# Dimmer_atmega328.net
KiCad netlist of a schematic drawn in EAGLE
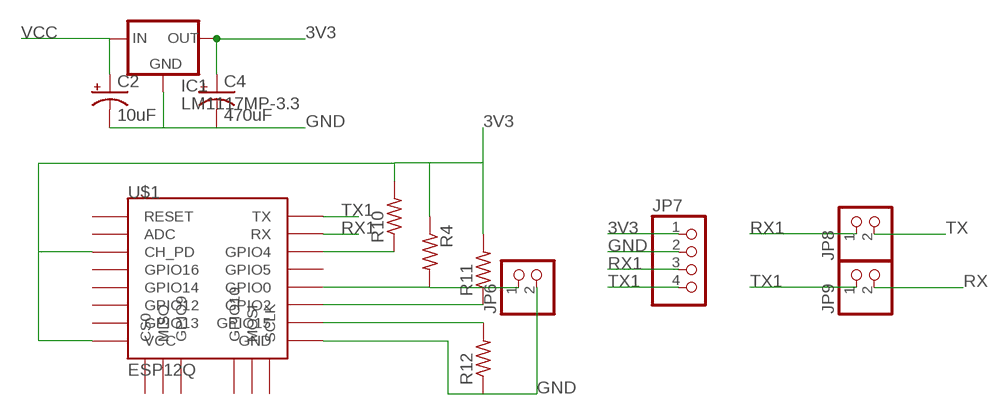
[diagram p0: schematic, sheet 1]
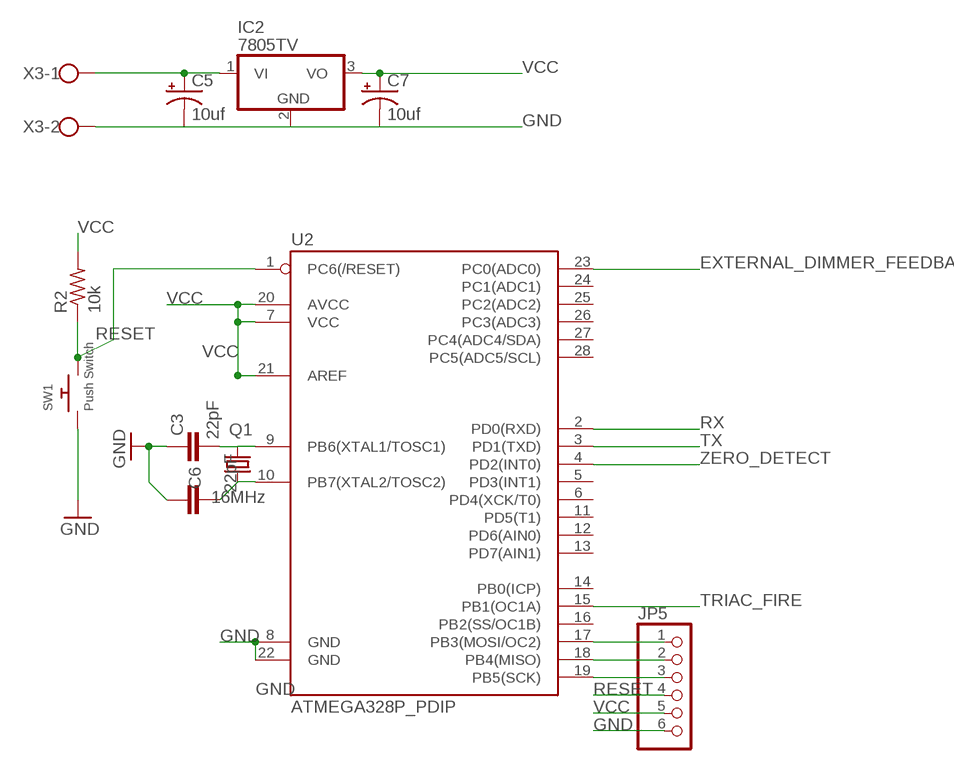
[diagram p1: schematic, sheet 2]
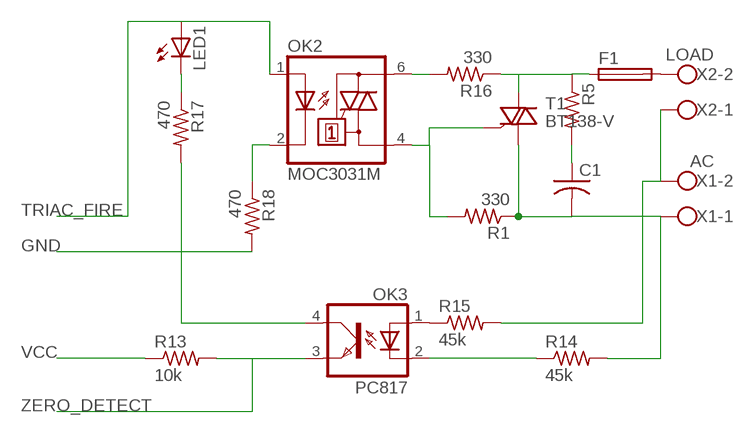
[diagram p2: schematic, sheet 3]
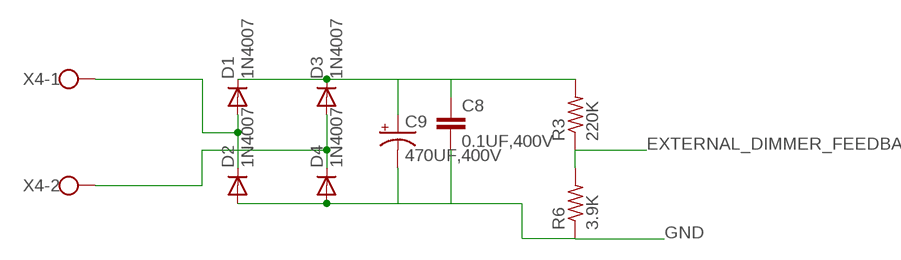
[diagram p3: schematic, sheet 4]

(export (version "E")
  (design (tool "Eeschema 10.0.6"))
  (components
    (comp (ref "C3")
      (value "22pF")
      (footprint "eagle-import:CAP-PTH-SMALL")
      (libsource (lib "eagle-import") (part "CAPPTH"))
    )
    (comp (ref "C5")
      (value "10uf")
      (footprint "eagle-import:E2,5-6")
      (libsource (lib "eagle-import") (part "rcl_CPOL-USE2.5-6"))
    )
    (comp (ref "C6")
      (value "22pF")
      (footprint "eagle-import:CAP-PTH-SMALL")
      (libsource (lib "eagle-import") (part "CAPPTH"))
    )
    (comp (ref "C7")
      (value "10uf")
      (footprint "eagle-import:E2,5-6")
      (libsource (lib "eagle-import") (part "rcl_CPOL-USE2.5-6"))
    )
    (comp (ref "IC2")
      (value "7805TV")
      (footprint "eagle-import:TO220V")
      (libsource (lib "eagle-import") (part "78TV05"))
    )
    (comp (ref "JP5")
      (value "PINHD-1X6")
      (footprint "eagle-import:1X06")
      (libsource (lib "eagle-import") (part "PINHD-1X6"))
    )
    (comp (ref "Q1")
      (value "16MHz")
      (footprint "eagle-import:HC49US")
      (libsource (lib "eagle-import") (part "CRYSTALHC49US"))
    )
    (comp (ref "R2")
      (value "10k")
      (footprint "eagle-import:0207_10")
      (libsource (lib "eagle-import") (part "resistor_R-US_0207/10"))
    )
    (comp (ref "SW1")
      (value "Push Switch")
      (footprint "eagle-import:TACT_PANA-EVQ")
      (libsource (lib "eagle-import") (part "SWITCH_PUSHBUTTONEVQ-PE"))
    )
    (comp (ref "U2")
      (value "ATMEGA328P_PDIP")
      (footprint "eagle-import:DIL28-3")
      (libsource (lib "eagle-import") (part "ATMEGA328P_PDIP"))
    )
    (comp (ref "X3")
      (value "W237-102")
      (footprint "eagle-import:W237-102")
      (fields (field (name "MPN") "237-102"))
      (libsource (lib "eagle-import") (part "con-wago-500_W237-102"))
    )
    (comp (ref "C8")
      (value "0.1UF,400V")
      (footprint "eagle-import:C102-054X133")
      (libsource (lib "eagle-import") (part "C-EU102-054X133"))
    )
    (comp (ref "C9")
      (value "470UF,400V")
      (footprint "eagle-import:E7,5-18")
      (libsource (lib "eagle-import") (part "CPOL-USE7.5-18"))
    )
    (comp (ref "D1")
      (value "1N4007")
      (footprint "eagle-import:DO41-10")
      (libsource (lib "eagle-import") (part "1N4004"))
    )
    (comp (ref "D2")
      (value "1N4007")
      (footprint "eagle-import:DO41-10")
      (libsource (lib "eagle-import") (part "1N4004"))
    )
    (comp (ref "D3")
      (value "1N4007")
      (footprint "eagle-import:DO41-10")
      (libsource (lib "eagle-import") (part "1N4004"))
    )
    (comp (ref "D4")
      (value "1N4007")
      (footprint "eagle-import:DO41-10")
      (libsource (lib "eagle-import") (part "1N4004"))
    )
    (comp (ref "R3")
      (value "220K")
      (footprint "eagle-import:0207_10")
      (libsource (lib "eagle-import") (part "R-US_0207/10"))
    )
    (comp (ref "R6")
      (value "3.9K")
      (footprint "eagle-import:0207_10")
      (libsource (lib "eagle-import") (part "R-US_0207/10"))
    )
    (comp (ref "X4")
      (value "W237-102")
      (footprint "eagle-import:W237-102")
      (fields (field (name "MPN") "237-102"))
      (libsource (lib "eagle-import") (part "W237-102"))
    )
    (comp (ref "C2")
      (value "10uF")
      (footprint "eagle-import:E2,5-6")
      (libsource (lib "eagle-import") (part "rcl_CPOL-USE2.5-6"))
    )
    (comp (ref "C4")
      (value "470uF")
      (footprint "eagle-import:E5-8,5")
      (libsource (lib "eagle-import") (part "rcl_CPOL-USE5-8.5"))
    )
    (comp (ref "IC1")
      (value "LM1117MP-3.3")
      (footprint "eagle-import:SOT223")
      (fields (field (name "MF") "Texas Instruments"))
      (libsource (lib "eagle-import") (part "LM1117?-MP3.3"))
    )
    (comp (ref "JP6")
      (value "PINHD-1X2")
      (footprint "eagle-import:1X02")
      (libsource (lib "eagle-import") (part "PINHD-1X2"))
    )
    (comp (ref "JP7")
      (value "PINHD-1X4")
      (footprint "eagle-import:1X04")
      (libsource (lib "eagle-import") (part "PINHD-1X4"))
    )
    (comp (ref "JP8")
      (value "PINHD-1X2")
      (footprint "eagle-import:1X02")
      (libsource (lib "eagle-import") (part "PINHD-1X2"))
    )
    (comp (ref "JP9")
      (value "PINHD-1X2")
      (footprint "eagle-import:1X02")
      (libsource (lib "eagle-import") (part "PINHD-1X2"))
    )
    (comp (ref "R4")
      (value "R-US_0207/10")
      (footprint "eagle-import:0207_10")
      (libsource (lib "eagle-import") (part "rcl_R-US_0207/10"))
    )
    (comp (ref "R10")
      (value "R-US_0207/10")
      (footprint "eagle-import:0207_10")
      (libsource (lib "eagle-import") (part "rcl_R-US_0207/10"))
    )
    (comp (ref "R11")
      (value "R-US_0207/10")
      (footprint "eagle-import:0207_10")
      (libsource (lib "eagle-import") (part "rcl_R-US_0207/10"))
    )
    (comp (ref "R12")
      (value "R-US_0207/10")
      (footprint "eagle-import:0207_10")
      (libsource (lib "eagle-import") (part "rcl_R-US_0207/10"))
    )
    (comp (ref "U$1")
      (value "ESP12Q")
      (footprint "eagle-import:ESP12Q")
      (libsource (lib "eagle-import") (part "ESP12Q"))
    )
    (comp (ref "C1")
      (value "C-US150-091X182")
      (footprint "eagle-import:C150-091X182")
      (libsource (lib "eagle-import") (part "C-US150-091X182"))
    )
    (comp (ref "F1")
      (value "GSH15")
      (footprint "eagle-import:GSH15")
      (fields (field (name "MPN") "64900001039"))
      (libsource (lib "eagle-import") (part "GSH15"))
    )
    (comp (ref "LED1")
      (value "LED3MM")
      (footprint "eagle-import:LED3MM")
      (libsource (lib "eagle-import") (part "LED3MM"))
    )
    (comp (ref "OK2")
      (value "MOC3031M")
      (footprint "eagle-import:DIL06")
      (fields (field (name "MF") "FAIRCHILD SEMICONDUCTOR"))
      (libsource (lib "eagle-import") (part "MOC3031M"))
    )
    (comp (ref "OK3")
      (value "PC817")
      (footprint "eagle-import:DIL04")
      (fields (field (name "MPN") "PC817X4J000F"))
      (libsource (lib "eagle-import") (part "PC817"))
    )
    (comp (ref "R1")
      (value "330")
      (footprint "eagle-import:0207_10")
      (libsource (lib "eagle-import") (part "resistor_R-US_0207/10"))
    )
    (comp (ref "R5")
      (value "R-US_0411/15")
      (footprint "eagle-import:0411_15")
      (libsource (lib "eagle-import") (part "resistor_R-US_0411/15"))
    )
    (comp (ref "R13")
      (value "10k")
      (footprint "eagle-import:0207_10")
      (libsource (lib "eagle-import") (part "resistor_R-US_0207/10"))
    )
    (comp (ref "R14")
      (value "45k")
      (footprint "eagle-import:0207_10")
      (libsource (lib "eagle-import") (part "resistor_R-US_0207/10"))
    )
    (comp (ref "R15")
      (value "45k")
      (footprint "eagle-import:0207_10")
      (libsource (lib "eagle-import") (part "resistor_R-US_0207/10"))
    )
    (comp (ref "R16")
      (value "330")
      (footprint "eagle-import:0207_10")
      (libsource (lib "eagle-import") (part "resistor_R-US_0207/10"))
    )
    (comp (ref "R17")
      (value "470")
      (footprint "eagle-import:0207_10")
      (libsource (lib "eagle-import") (part "resistor_R-US_0207/10"))
    )
    (comp (ref "R18")
      (value "470")
      (footprint "eagle-import:0207_10")
      (libsource (lib "eagle-import") (part "resistor_R-US_0207/10"))
    )
    (comp (ref "T1")
      (value "BT138-V")
      (footprint "eagle-import:TO220BV")
      (libsource (lib "eagle-import") (part "BT138-V"))
    )
    (comp (ref "X1")
      (value "AC")
      (footprint "eagle-import:W237-102")
      (fields (field (name "MPN") "237-102"))
      (libsource (lib "eagle-import") (part "con-wago-500_W237-102"))
    )
    (comp (ref "X2")
      (value "LOAD")
      (footprint "eagle-import:W237-102")
      (fields (field (name "MPN") "237-102"))
      (libsource (lib "eagle-import") (part "con-wago-500_W237-102"))
    )
  )
  (nets
    (net (code "1") (name "3V3") (class "Default")
      (node (ref "C4") (pin "+") (pinfunction "+_+") (pintype "passive"))
      (node (ref "IC1") (pin "2") (pinfunction "OUT_2") (pintype "passive"))
      (node (ref "IC1") (pin "4") (pinfunction "OUT_4") (pintype "passive"))
      (node (ref "JP7") (pin "1") (pinfunction "1_1") (pintype "passive"))
      (node (ref "R10") (pin "2") (pinfunction "2_2") (pintype "passive"))
      (node (ref "R11") (pin "2") (pinfunction "2_2") (pintype "passive"))
      (node (ref "R4") (pin "1") (pinfunction "1_1") (pintype "passive"))
      (node (ref "U$1") (pin "CH_PD") (pinfunction "CH_PD_CH_PD") (pintype "bidirectional"))
      (node (ref "U$1") (pin "VCC") (pinfunction "VCC_VCC") (pintype "bidirectional"))
    )
    (net (code "2") (name "EXTERNAL_DIMMER_FEEDBACK") (class "Default")
      (node (ref "R3") (pin "1") (pinfunction "1_1") (pintype "passive"))
      (node (ref "R6") (pin "2") (pinfunction "2_2") (pintype "passive"))
      (node (ref "U2") (pin "23") (pinfunction "PC0(ADC0)_23") (pintype "bidirectional"))
    )
    (net (code "3") (name "GND") (class "Default")
      (node (ref "C2") (pin "-") (pinfunction "-_-") (pintype "passive"))
      (node (ref "C3") (pin "1") (pinfunction "1_1") (pintype "passive"))
      (node (ref "C4") (pin "-") (pinfunction "-_-") (pintype "passive"))
      (node (ref "C5") (pin "-") (pinfunction "-_-") (pintype "passive"))
      (node (ref "C6") (pin "1") (pinfunction "1_1") (pintype "passive"))
      (node (ref "C7") (pin "-") (pinfunction "-_-") (pintype "passive"))
      (node (ref "C8") (pin "2") (pinfunction "2_2") (pintype "passive"))
      (node (ref "C9") (pin "-") (pinfunction "-_-") (pintype "passive"))
      (node (ref "D2") (pin "A") (pinfunction "A_A") (pintype "passive"))
      (node (ref "D4") (pin "A") (pinfunction "A_A") (pintype "passive"))
      (node (ref "IC1") (pin "1") (pinfunction "GND_1") (pintype "input"))
      (node (ref "IC2") (pin "2") (pinfunction "GND_2") (pintype "passive"))
      (node (ref "JP5") (pin "6") (pinfunction "6_6") (pintype "passive"))
      (node (ref "JP6") (pin "2") (pinfunction "2_2") (pintype "passive"))
      (node (ref "JP7") (pin "2") (pinfunction "2_2") (pintype "passive"))
      (node (ref "OK3") (pin "4") (pinfunction "COL_4") (pintype "passive"))
      (node (ref "R12") (pin "1") (pinfunction "1_1") (pintype "passive"))
      (node (ref "R17") (pin "2") (pinfunction "2_2") (pintype "passive"))
      (node (ref "R18") (pin "2") (pinfunction "2_2") (pintype "passive"))
      (node (ref "R6") (pin "1") (pinfunction "1_1") (pintype "passive"))
      (node (ref "SW1") (pin "P$1") (pinfunction "P$1_P$1") (pintype "passive"))
      (node (ref "U$1") (pin "GND") (pinfunction "GND_GND") (pintype "bidirectional"))
      (node (ref "U2") (pin "22") (pinfunction "GND_22") (pintype "bidirectional"))
      (node (ref "U2") (pin "8") (pinfunction "GND_8") (pintype "bidirectional"))
      (node (ref "X3") (pin "2") (pinfunction "KL_2") (pintype "passive"))
    )
    (net (code "4") (name "Net-(C1-Pad1)") (class "Default")
      (node (ref "C1") (pin "1") (pinfunction "1_1") (pintype "passive"))
      (node (ref "R5") (pin "2") (pinfunction "2_2") (pintype "passive"))
    )
    (net (code "5") (name "Net-(C8-Pad1)") (class "Default")
      (node (ref "C8") (pin "1") (pinfunction "1_1") (pintype "passive"))
      (node (ref "C9") (pin "+") (pinfunction "+_+") (pintype "passive"))
      (node (ref "D1") (pin "C") (pinfunction "C_C") (pintype "passive"))
      (node (ref "D3") (pin "C") (pinfunction "C_C") (pintype "passive"))
      (node (ref "R3") (pin "2") (pinfunction "2_2") (pintype "passive"))
    )
    (net (code "6") (name "Net-(IC2-VI)") (class "Default")
      (node (ref "C5") (pin "+") (pinfunction "+_+") (pintype "passive"))
      (node (ref "IC2") (pin "1") (pinfunction "VI_1") (pintype "input"))
      (node (ref "X3") (pin "1") (pinfunction "KL_1") (pintype "passive"))
    )
    (net (code "7") (name "Net-(JP6-Pad1)") (class "Default")
      (node (ref "JP6") (pin "1") (pinfunction "1_1") (pintype "passive"))
      (node (ref "R4") (pin "2") (pinfunction "2_2") (pintype "passive"))
      (node (ref "U$1") (pin "GPIO0") (pinfunction "GPIO0_GPIO0") (pintype "bidirectional"))
    )
    (net (code "8") (name "Net-(LED1-C)") (class "Default")
      (node (ref "LED1") (pin "K") (pinfunction "C_K") (pintype "passive"))
      (node (ref "R17") (pin "1") (pinfunction "1_1") (pintype "passive"))
    )
    (net (code "9") (name "Net-(OK2-A1)") (class "Default")
      (node (ref "OK2") (pin "4") (pinfunction "A1_4") (pintype "passive"))
      (node (ref "R1") (pin "2") (pinfunction "2_2") (pintype "passive"))
      (node (ref "T1") (pin "G") (pinfunction "G_G") (pintype "passive"))
    )
    (net (code "10") (name "Net-(OK2-A2)") (class "Default")
      (node (ref "OK2") (pin "6") (pinfunction "A2_6") (pintype "passive"))
      (node (ref "R16") (pin "2") (pinfunction "2_2") (pintype "passive"))
    )
    (net (code "11") (name "Net-(OK2-C)") (class "Default")
      (node (ref "OK2") (pin "2") (pinfunction "C_2") (pintype "passive"))
      (node (ref "R18") (pin "1") (pinfunction "1_1") (pintype "passive"))
    )
    (net (code "12") (name "Net-(OK3-A)") (class "Default")
      (node (ref "OK3") (pin "1") (pinfunction "A_1") (pintype "passive"))
      (node (ref "R15") (pin "1") (pinfunction "1_1") (pintype "passive"))
    )
    (net (code "13") (name "Net-(OK3-C)") (class "Default")
      (node (ref "OK3") (pin "2") (pinfunction "C_2") (pintype "passive"))
      (node (ref "R14") (pin "1") (pinfunction "1_1") (pintype "passive"))
    )
    (net (code "14") (name "Net-(R10-Pad1)") (class "Default")
      (node (ref "R10") (pin "1") (pinfunction "1_1") (pintype "passive"))
      (node (ref "U$1") (pin "GPIO4") (pinfunction "GPIO4_GPIO4") (pintype "bidirectional"))
    )
    (net (code "15") (name "Net-(R11-Pad1)") (class "Default")
      (node (ref "R11") (pin "1") (pinfunction "1_1") (pintype "passive"))
      (node (ref "U$1") (pin "GPIO2") (pinfunction "GPIO2_GPIO2") (pintype "bidirectional"))
    )
    (net (code "16") (name "Net-(R12-Pad2)") (class "Default")
      (node (ref "R12") (pin "2") (pinfunction "2_2") (pintype "passive"))
      (node (ref "U$1") (pin "GPIO15") (pinfunction "GPIO15_GPIO15") (pintype "bidirectional"))
    )
    (net (code "17") (name "Net-(T1-A1)") (class "Default")
      (node (ref "C1") (pin "2") (pinfunction "2_2") (pintype "passive"))
      (node (ref "R1") (pin "1") (pinfunction "1_1") (pintype "passive"))
      (node (ref "R14") (pin "2") (pinfunction "2_2") (pintype "passive"))
      (node (ref "T1") (pin "T1") (pinfunction "A1_T1") (pintype "passive"))
      (node (ref "X1") (pin "1") (pinfunction "KL_1") (pintype "passive"))
    )
    (net (code "18") (name "Net-(T1-A2)") (class "Default")
      (node (ref "F1") (pin "1") (pinfunction "1_1") (pintype "passive"))
      (node (ref "R16") (pin "1") (pinfunction "1_1") (pintype "passive"))
      (node (ref "R5") (pin "1") (pinfunction "1_1") (pintype "passive"))
      (node (ref "T1") (pin "T2") (pinfunction "A2_T2") (pintype "passive"))
    )
    (net (code "19") (name "Net-(U2-PB3(MOSI{slash}OC2))") (class "Default")
      (node (ref "JP5") (pin "1") (pinfunction "1_1") (pintype "passive"))
      (node (ref "U2") (pin "17") (pinfunction "PB3(MOSI/OC2)_17") (pintype "bidirectional"))
    )
    (net (code "20") (name "Net-(U2-PB4(MISO))") (class "Default")
      (node (ref "JP5") (pin "2") (pinfunction "2_2") (pintype "passive"))
      (node (ref "U2") (pin "18") (pinfunction "PB4(MISO)_18") (pintype "bidirectional"))
    )
    (net (code "21") (name "Net-(U2-PB5(SCK))") (class "Default")
      (node (ref "JP5") (pin "3") (pinfunction "3_3") (pintype "passive"))
      (node (ref "U2") (pin "19") (pinfunction "PB5(SCK)_19") (pintype "bidirectional"))
    )
    (net (code "22") (name "Net-(U2-PB6(XTAL1{slash}TOSC1))") (class "Default")
      (node (ref "C3") (pin "2") (pinfunction "2_2") (pintype "passive"))
      (node (ref "Q1") (pin "2") (pinfunction "2_2") (pintype "passive"))
      (node (ref "U2") (pin "9") (pinfunction "PB6(XTAL1/TOSC1)_9") (pintype "bidirectional"))
    )
    (net (code "23") (name "Net-(U2-PB7(XTAL2{slash}TOSC2))") (class "Default")
      (node (ref "C6") (pin "2") (pinfunction "2_2") (pintype "passive"))
      (node (ref "Q1") (pin "1") (pinfunction "1_1") (pintype "passive"))
      (node (ref "U2") (pin "10") (pinfunction "PB7(XTAL2/TOSC2)_10") (pintype "bidirectional"))
    )
    (net (code "24") (name "Net-(X1B-KL)") (class "Default")
      (node (ref "R15") (pin "2") (pinfunction "2_2") (pintype "passive"))
      (node (ref "X1") (pin "2") (pinfunction "KL_2") (pintype "passive"))
      (node (ref "X2") (pin "1") (pinfunction "KL_1") (pintype "passive"))
    )
    (net (code "25") (name "Net-(X2B-KL)") (class "Default")
      (node (ref "F1") (pin "2") (pinfunction "2_2") (pintype "passive"))
      (node (ref "X2") (pin "2") (pinfunction "KL_2") (pintype "passive"))
    )
    (net (code "26") (name "Net-(X4A-KL)") (class "Default")
      (node (ref "D1") (pin "A") (pinfunction "A_A") (pintype "passive"))
      (node (ref "D2") (pin "C") (pinfunction "C_C") (pintype "passive"))
      (node (ref "X4") (pin "1") (pinfunction "KL_1") (pintype "passive"))
    )
    (net (code "27") (name "Net-(X4B-KL)") (class "Default")
      (node (ref "D3") (pin "A") (pinfunction "A_A") (pintype "passive"))
      (node (ref "D4") (pin "C") (pinfunction "C_C") (pintype "passive"))
      (node (ref "X4") (pin "2") (pinfunction "KL_2") (pintype "passive"))
    )
    (net (code "28") (name "RESET") (class "Default")
      (node (ref "JP5") (pin "4") (pinfunction "4_4") (pintype "passive"))
      (node (ref "R2") (pin "1") (pinfunction "1_1") (pintype "passive"))
      (node (ref "SW1") (pin "P$2") (pinfunction "P$2_P$2") (pintype "passive"))
      (node (ref "U2") (pin "1") (pinfunction "PC6(/RESET)_1") (pintype "bidirectional"))
    )
    (net (code "29") (name "RX") (class "Default")
      (node (ref "JP9") (pin "2") (pinfunction "2_2") (pintype "passive"))
      (node (ref "U2") (pin "2") (pinfunction "PD0(RXD)_2") (pintype "bidirectional"))
    )
    (net (code "30") (name "RX1") (class "Default")
      (node (ref "JP7") (pin "3") (pinfunction "3_3") (pintype "passive"))
      (node (ref "JP8") (pin "1") (pinfunction "1_1") (pintype "passive"))
      (node (ref "U$1") (pin "RX") (pinfunction "RX_RX") (pintype "bidirectional"))
    )
    (net (code "31") (name "TRIAC_FIRE") (class "Default")
      (node (ref "LED1") (pin "A") (pinfunction "A_A") (pintype "passive"))
      (node (ref "OK2") (pin "1") (pinfunction "A_1") (pintype "passive"))
      (node (ref "U2") (pin "15") (pinfunction "PB1(OC1A)_15") (pintype "bidirectional"))
    )
    (net (code "32") (name "TX") (class "Default")
      (node (ref "JP8") (pin "2") (pinfunction "2_2") (pintype "passive"))
      (node (ref "U2") (pin "3") (pinfunction "PD1(TXD)_3") (pintype "bidirectional"))
    )
    (net (code "33") (name "TX1") (class "Default")
      (node (ref "JP7") (pin "4") (pinfunction "4_4") (pintype "passive"))
      (node (ref "JP9") (pin "1") (pinfunction "1_1") (pintype "passive"))
      (node (ref "U$1") (pin "TX") (pinfunction "TX_TX") (pintype "bidirectional"))
    )
    (net (code "34") (name "VCC") (class "Default")
      (node (ref "C2") (pin "+") (pinfunction "+_+") (pintype "passive"))
      (node (ref "C7") (pin "+") (pinfunction "+_+") (pintype "passive"))
      (node (ref "IC1") (pin "3") (pinfunction "IN_3") (pintype "input"))
      (node (ref "IC2") (pin "3") (pinfunction "VO_3") (pintype "passive"))
      (node (ref "JP5") (pin "5") (pinfunction "5_5") (pintype "passive"))
      (node (ref "R13") (pin "1") (pinfunction "1_1") (pintype "passive"))
      (node (ref "R2") (pin "2") (pinfunction "2_2") (pintype "passive"))
      (node (ref "U2") (pin "20") (pinfunction "AVCC_20") (pintype "bidirectional"))
      (node (ref "U2") (pin "21") (pinfunction "AREF_21") (pintype "bidirectional"))
      (node (ref "U2") (pin "7") (pinfunction "VCC_7") (pintype "bidirectional"))
    )
    (net (code "35") (name "ZERO_DETECT") (class "Default")
      (node (ref "OK3") (pin "3") (pinfunction "EMIT_3") (pintype "passive"))
      (node (ref "R13") (pin "2") (pinfunction "2_2") (pintype "passive"))
      (node (ref "U2") (pin "4") (pinfunction "PD2(INT0)_4") (pintype "bidirectional"))
    )
    (net (code "36") (name "unconnected-(U$1-PadADC)") (class "Default")
      (node (ref "U$1") (pin "ADC") (pinfunction "ADC_ADC") (pintype "bidirectional"))
    )
    (net (code "37") (name "unconnected-(U$1-PadCS0)") (class "Default")
      (node (ref "U$1") (pin "CS0") (pinfunction "CS0_CS0") (pintype "bidirectional"))
    )
    (net (code "38") (name "unconnected-(U$1-PadGPIO5)") (class "Default")
      (node (ref "U$1") (pin "GPIO5") (pinfunction "GPIO5_GPIO5") (pintype "bidirectional"))
    )
    (net (code "39") (name "unconnected-(U$1-PadGPIO9)") (class "Default")
      (node (ref "U$1") (pin "GPIO9") (pinfunction "GPIO9_GPIO9") (pintype "bidirectional"))
    )
    (net (code "40") (name "unconnected-(U$1-PadGPIO10)") (class "Default")
      (node (ref "U$1") (pin "GPIO10") (pinfunction "GPIO10_GPIO10") (pintype "bidirectional"))
    )
    (net (code "41") (name "unconnected-(U$1-PadGPIO12)") (class "Default")
      (node (ref "U$1") (pin "GPIO12") (pinfunction "GPIO12_GPIO12") (pintype "bidirectional"))
    )
    (net (code "42") (name "unconnected-(U$1-PadGPIO13)") (class "Default")
      (node (ref "U$1") (pin "GPIO13") (pinfunction "GPIO13_GPIO13") (pintype "bidirectional"))
    )
    (net (code "43") (name "unconnected-(U$1-PadGPIO14)") (class "Default")
      (node (ref "U$1") (pin "GPIO14") (pinfunction "GPIO14_GPIO14") (pintype "bidirectional"))
    )
    (net (code "44") (name "unconnected-(U$1-PadGPIO16)") (class "Default")
      (node (ref "U$1") (pin "GPIO16") (pinfunction "GPIO16_GPIO16") (pintype "bidirectional"))
    )
    (net (code "45") (name "unconnected-(U$1-PadMISO)") (class "Default")
      (node (ref "U$1") (pin "MISO") (pinfunction "MISO_MISO") (pintype "bidirectional"))
    )
    (net (code "46") (name "unconnected-(U$1-PadMOSI)") (class "Default")
      (node (ref "U$1") (pin "MOSI") (pinfunction "MOSI_MOSI") (pintype "bidirectional"))
    )
    (net (code "47") (name "unconnected-(U$1-PadRESET)") (class "Default")
      (node (ref "U$1") (pin "RESET") (pinfunction "RESET_RESET") (pintype "bidirectional"))
    )
    (net (code "48") (name "unconnected-(U$1-PadSCLK)") (class "Default")
      (node (ref "U$1") (pin "SCLK") (pinfunction "SCLK_SCLK") (pintype "bidirectional"))
    )
    (net (code "49") (name "unconnected-(U2-PB0(ICP)-Pad14)") (class "Default")
      (node (ref "U2") (pin "14") (pinfunction "PB0(ICP)_14") (pintype "bidirectional"))
    )
    (net (code "50") (name "unconnected-(U2-PB2(SS{slash}OC1B)-Pad16)") (class "Default")
      (node (ref "U2") (pin "16") (pinfunction "PB2(SS/OC1B)_16") (pintype "bidirectional"))
    )
    (net (code "51") (name "unconnected-(U2-PC1(ADC1)-Pad24)") (class "Default")
      (node (ref "U2") (pin "24") (pinfunction "PC1(ADC1)_24") (pintype "bidirectional"))
    )
    (net (code "52") (name "unconnected-(U2-PC2(ADC2)-Pad25)") (class "Default")
      (node (ref "U2") (pin "25") (pinfunction "PC2(ADC2)_25") (pintype "bidirectional"))
    )
    (net (code "53") (name "unconnected-(U2-PC3(ADC3)-Pad26)") (class "Default")
      (node (ref "U2") (pin "26") (pinfunction "PC3(ADC3)_26") (pintype "bidirectional"))
    )
    (net (code "54") (name "unconnected-(U2-PC4(ADC4{slash}SDA)-Pad27)") (class "Default")
      (node (ref "U2") (pin "27") (pinfunction "PC4(ADC4/SDA)_27") (pintype "bidirectional"))
    )
    (net (code "55") (name "unconnected-(U2-PC5(ADC5{slash}SCL)-Pad28)") (class "Default")
      (node (ref "U2") (pin "28") (pinfunction "PC5(ADC5/SCL)_28") (pintype "bidirectional"))
    )
    (net (code "56") (name "unconnected-(U2-PD3(INT1)-Pad5)") (class "Default")
      (node (ref "U2") (pin "5") (pinfunction "PD3(INT1)_5") (pintype "bidirectional"))
    )
    (net (code "57") (name "unconnected-(U2-PD4(XCK{slash}T0)-Pad6)") (class "Default")
      (node (ref "U2") (pin "6") (pinfunction "PD4(XCK/T0)_6") (pintype "bidirectional"))
    )
    (net (code "58") (name "unconnected-(U2-PD5(T1)-Pad11)") (class "Default")
      (node (ref "U2") (pin "11") (pinfunction "PD5(T1)_11") (pintype "bidirectional"))
    )
    (net (code "59") (name "unconnected-(U2-PD6(AIN0)-Pad12)") (class "Default")
      (node (ref "U2") (pin "12") (pinfunction "PD6(AIN0)_12") (pintype "bidirectional"))
    )
    (net (code "60") (name "unconnected-(U2-PD7(AIN1)-Pad13)") (class "Default")
      (node (ref "U2") (pin "13") (pinfunction "PD7(AIN1)_13") (pintype "bidirectional"))
    )
  )
)
